# persephone_A_v1.net
KiCad netlist of a schematic drawn in EAGLE
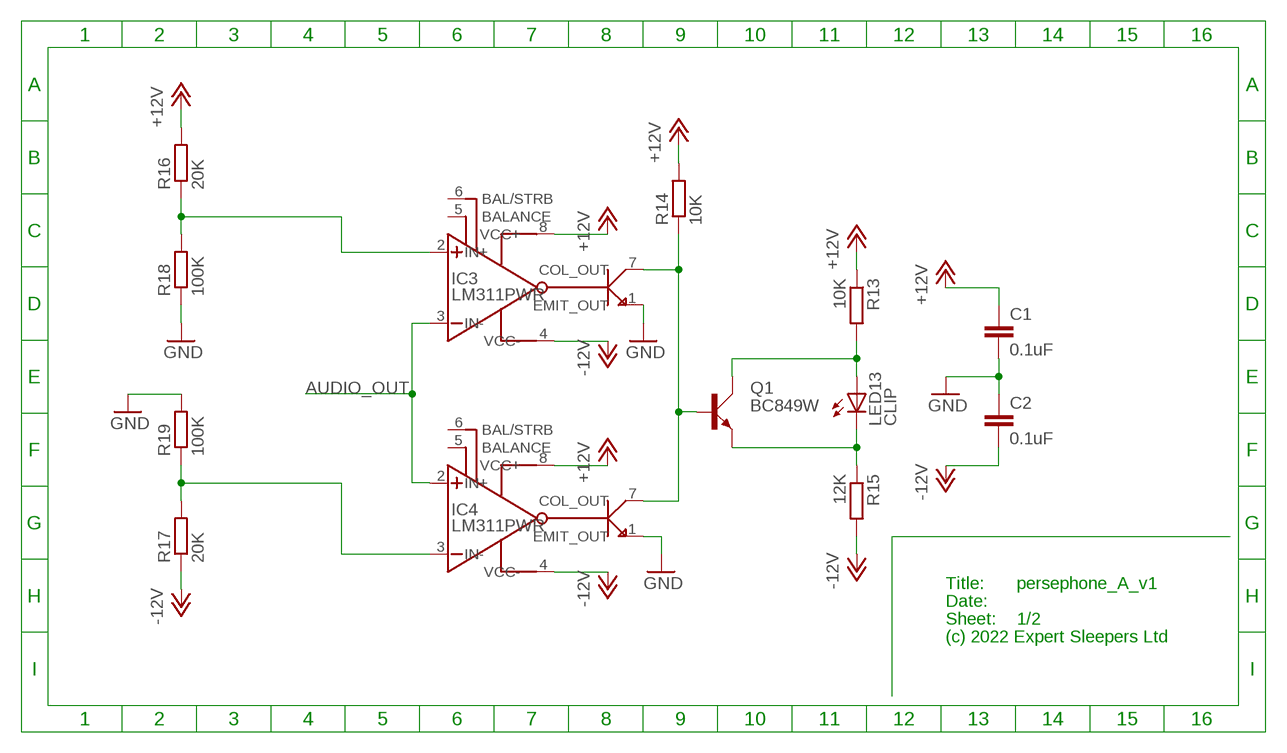
[diagram p0: schematic, sheet 1]
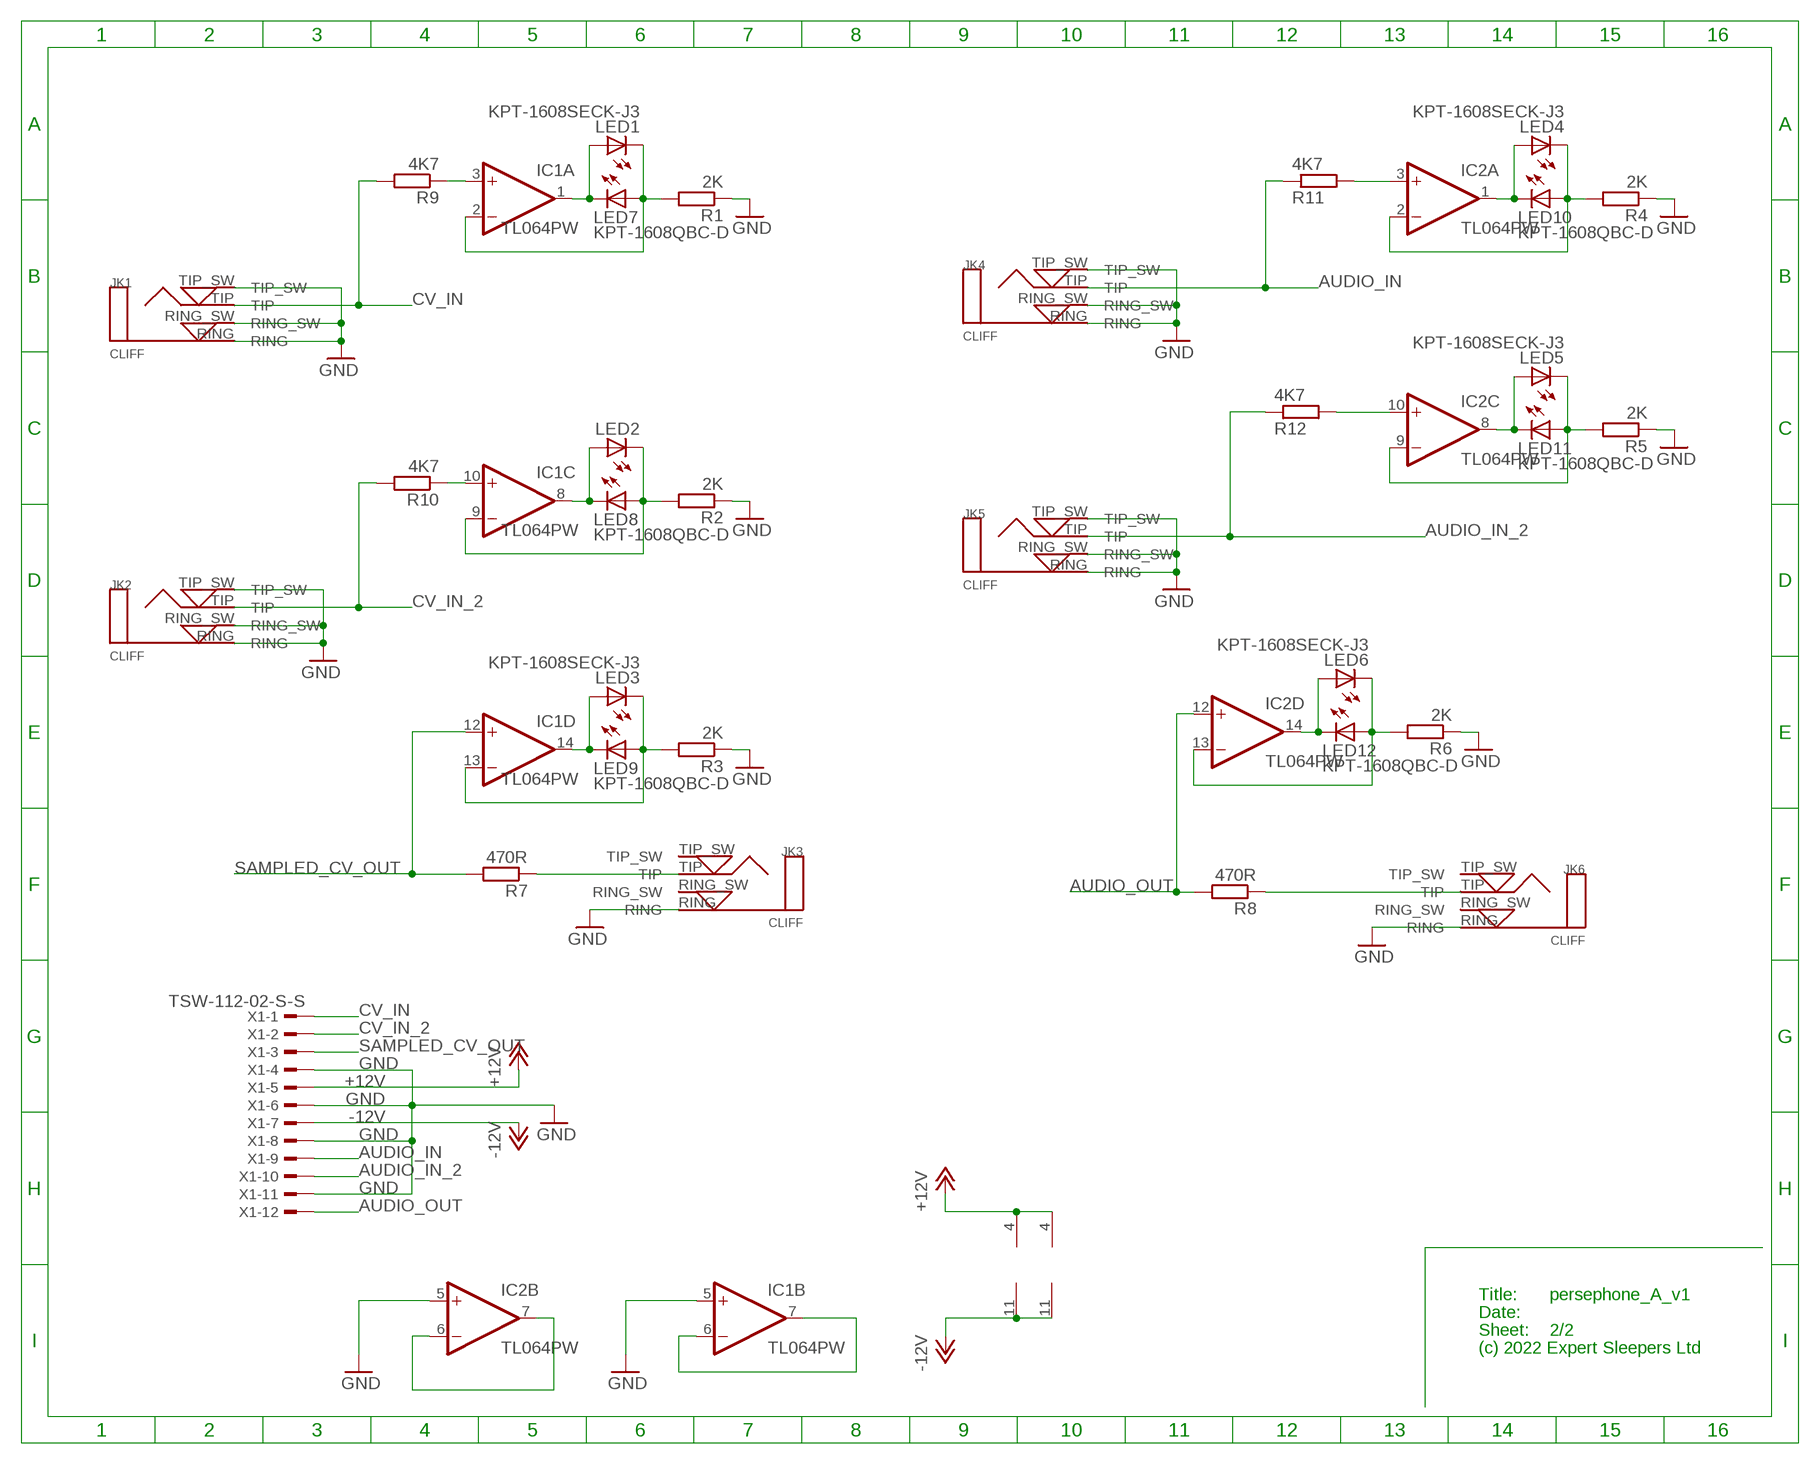
[diagram p1: schematic, sheet 2]

(export (version "E")
  (design (tool "Eeschema 10.0.6"))
  (components
    (comp (ref "IC1")
      (value "TL064PW")
      (footprint "eagle-import:PW_R-PDSO-G14")
      (libsource (lib "eagle-import") (part "TL074PW"))
    )
    (comp (ref "IC2")
      (value "TL064PW")
      (footprint "eagle-import:PW_R-PDSO-G14")
      (libsource (lib "eagle-import") (part "TL074PW"))
    )
    (comp (ref "JK1")
      (value "CLIFF")
      (footprint "eagle-import:CLIFF3.5MMPCB")
      (libsource (lib "eagle-import") (part "CLIFF3.5MM_PCB_SW_JK"))
    )
    (comp (ref "JK2")
      (value "CLIFF")
      (footprint "eagle-import:CLIFF3.5MMPCB")
      (libsource (lib "eagle-import") (part "CLIFF3.5MM_PCB_SW_JK"))
    )
    (comp (ref "JK3")
      (value "CLIFF")
      (footprint "eagle-import:CLIFF3.5MMPCB")
      (libsource (lib "eagle-import") (part "CLIFF3.5MM_PCB_SW_JK"))
    )
    (comp (ref "JK4")
      (value "CLIFF")
      (footprint "eagle-import:CLIFF3.5MMPCB")
      (libsource (lib "eagle-import") (part "CLIFF3.5MM_PCB_SW_JK"))
    )
    (comp (ref "JK5")
      (value "CLIFF")
      (footprint "eagle-import:CLIFF3.5MMPCB")
      (libsource (lib "eagle-import") (part "CLIFF3.5MM_PCB_SW_JK"))
    )
    (comp (ref "JK6")
      (value "CLIFF")
      (footprint "eagle-import:CLIFF3.5MMPCB")
      (libsource (lib "eagle-import") (part "CLIFF3.5MM_PCB_SW_JK"))
    )
    (comp (ref "LED1")
      (value "KPT-1608SECK-J3")
      (footprint "eagle-import:CHIPLED_0603_LEFT")
      (libsource (lib "eagle-import") (part "KPT-1608SECK-J3"))
    )
    (comp (ref "LED2")
      (value "KPT-1608SECK-J3")
      (footprint "eagle-import:CHIPLED_0603_LEFT")
      (libsource (lib "eagle-import") (part "KPT-1608SECK-J3"))
    )
    (comp (ref "LED3")
      (value "KPT-1608SECK-J3")
      (footprint "eagle-import:CHIPLED_0603_LEFT")
      (libsource (lib "eagle-import") (part "KPT-1608SECK-J3"))
    )
    (comp (ref "LED4")
      (value "KPT-1608SECK-J3")
      (footprint "eagle-import:CHIPLED_0603_LEFT")
      (libsource (lib "eagle-import") (part "KPT-1608SECK-J3"))
    )
    (comp (ref "LED5")
      (value "KPT-1608SECK-J3")
      (footprint "eagle-import:CHIPLED_0603_LEFT")
      (libsource (lib "eagle-import") (part "KPT-1608SECK-J3"))
    )
    (comp (ref "LED6")
      (value "KPT-1608SECK-J3")
      (footprint "eagle-import:CHIPLED_0603_LEFT")
      (libsource (lib "eagle-import") (part "KPT-1608SECK-J3"))
    )
    (comp (ref "LED7")
      (value "KPT-1608QBC-D")
      (footprint "eagle-import:CHIPLED_0603_RIGHT")
      (libsource (lib "eagle-import") (part "KPT-1608QBC-D"))
    )
    (comp (ref "LED8")
      (value "KPT-1608QBC-D")
      (footprint "eagle-import:CHIPLED_0603_RIGHT")
      (libsource (lib "eagle-import") (part "KPT-1608QBC-D"))
    )
    (comp (ref "LED9")
      (value "KPT-1608QBC-D")
      (footprint "eagle-import:CHIPLED_0603_RIGHT")
      (libsource (lib "eagle-import") (part "KPT-1608QBC-D"))
    )
    (comp (ref "LED10")
      (value "KPT-1608QBC-D")
      (footprint "eagle-import:CHIPLED_0603_RIGHT")
      (libsource (lib "eagle-import") (part "KPT-1608QBC-D"))
    )
    (comp (ref "LED11")
      (value "KPT-1608QBC-D")
      (footprint "eagle-import:CHIPLED_0603_RIGHT")
      (libsource (lib "eagle-import") (part "KPT-1608QBC-D"))
    )
    (comp (ref "LED12")
      (value "KPT-1608QBC-D")
      (footprint "eagle-import:CHIPLED_0603_RIGHT")
      (libsource (lib "eagle-import") (part "KPT-1608QBC-D"))
    )
    (comp (ref "R1")
      (value "2K")
      (footprint "eagle-import:R1206")
      (libsource (lib "eagle-import") (part "R-EU_R1206"))
    )
    (comp (ref "R2")
      (value "2K")
      (footprint "eagle-import:R1206")
      (libsource (lib "eagle-import") (part "R-EU_R1206"))
    )
    (comp (ref "R3")
      (value "2K")
      (footprint "eagle-import:R1206")
      (libsource (lib "eagle-import") (part "R-EU_R1206"))
    )
    (comp (ref "R4")
      (value "2K")
      (footprint "eagle-import:R1206")
      (libsource (lib "eagle-import") (part "R-EU_R1206"))
    )
    (comp (ref "R5")
      (value "2K")
      (footprint "eagle-import:R1206")
      (libsource (lib "eagle-import") (part "R-EU_R1206"))
    )
    (comp (ref "R6")
      (value "2K")
      (footprint "eagle-import:R1206")
      (libsource (lib "eagle-import") (part "R-EU_R1206"))
    )
    (comp (ref "R7")
      (value "470R")
      (footprint "eagle-import:R1206")
      (libsource (lib "eagle-import") (part "R-EU_R1206"))
    )
    (comp (ref "R8")
      (value "470R")
      (footprint "eagle-import:R1206")
      (libsource (lib "eagle-import") (part "R-EU_R1206"))
    )
    (comp (ref "R9")
      (value "4K7")
      (footprint "eagle-import:R1206")
      (libsource (lib "eagle-import") (part "R-EU_R1206"))
    )
    (comp (ref "R10")
      (value "4K7")
      (footprint "eagle-import:R1206")
      (libsource (lib "eagle-import") (part "R-EU_R1206"))
    )
    (comp (ref "R11")
      (value "4K7")
      (footprint "eagle-import:R1206")
      (libsource (lib "eagle-import") (part "R-EU_R1206"))
    )
    (comp (ref "R12")
      (value "4K7")
      (footprint "eagle-import:R1206")
      (libsource (lib "eagle-import") (part "R-EU_R1206"))
    )
    (comp (ref "X1")
      (value "TSW-112-02-S-S")
      (footprint "eagle-import:TSW-112-02-S-S")
      (libsource (lib "eagle-import") (part "TSW-112-02-S-S"))
    )
    (comp (ref "C1")
      (value "0.1uF")
      (footprint "eagle-import:C0402")
      (libsource (lib "eagle-import") (part "C-EUC0402"))
    )
    (comp (ref "C2")
      (value "0.1uF")
      (footprint "eagle-import:C0402")
      (libsource (lib "eagle-import") (part "C-EUC0402"))
    )
    (comp (ref "IC3")
      (value "LM311PWR")
      (footprint "eagle-import:SOP65P640X120-8N")
      (fields (field (name "MOUSER_PART_NUMBER") "595-LM311PWR"))
      (libsource (lib "eagle-import") (part "LM311PWR"))
    )
    (comp (ref "IC4")
      (value "LM311PWR")
      (footprint "eagle-import:SOP65P640X120-8N")
      (fields (field (name "MOUSER_PART_NUMBER") "595-LM311PWR"))
      (libsource (lib "eagle-import") (part "LM311PWR"))
    )
    (comp (ref "LED13")
      (value "CLIP")
      (footprint "eagle-import:L-710A8RS")
      (libsource (lib "eagle-import") (part "L-710A8RS/1SRD"))
    )
    (comp (ref "Q1")
      (value "BC849W")
      (footprint "eagle-import:SOT323")
      (libsource (lib "eagle-import") (part "BC849W"))
    )
    (comp (ref "R13")
      (value "10K")
      (footprint "eagle-import:R0603")
      (libsource (lib "eagle-import") (part "R-EU_R0603"))
    )
    (comp (ref "R14")
      (value "10K")
      (footprint "eagle-import:R0603")
      (libsource (lib "eagle-import") (part "R-EU_R0603"))
    )
    (comp (ref "R15")
      (value "12K")
      (footprint "eagle-import:R0603")
      (libsource (lib "eagle-import") (part "R-EU_R0603"))
    )
    (comp (ref "R16")
      (value "20K")
      (footprint "eagle-import:R0603")
      (libsource (lib "eagle-import") (part "R-EU_R0603"))
    )
    (comp (ref "R17")
      (value "20K")
      (footprint "eagle-import:R0603")
      (libsource (lib "eagle-import") (part "R-EU_R0603"))
    )
    (comp (ref "R18")
      (value "100K")
      (footprint "eagle-import:R0603")
      (libsource (lib "eagle-import") (part "R-EU_R0603"))
    )
    (comp (ref "R19")
      (value "100K")
      (footprint "eagle-import:R0603")
      (libsource (lib "eagle-import") (part "R-EU_R0603"))
    )
  )
  (nets
    (net (code "1") (name "+12V") (class "Default")
      (node (ref "C1") (pin "1") (pinfunction "1_1") (pintype "passive"))
      (node (ref "IC1") (pin "4") (pinfunction "V+_4") (pintype "power_in"))
      (node (ref "IC2") (pin "4") (pinfunction "V+_4") (pintype "power_in"))
      (node (ref "IC3") (pin "8") (pinfunction "VCC+_8") (pintype "power_in"))
      (node (ref "IC4") (pin "8") (pinfunction "VCC+_8") (pintype "power_in"))
      (node (ref "R13") (pin "1") (pinfunction "1_1") (pintype "passive"))
      (node (ref "R14") (pin "2") (pinfunction "2_2") (pintype "passive"))
      (node (ref "R16") (pin "2") (pinfunction "2_2") (pintype "passive"))
      (node (ref "X1") (pin "5") (pinfunction "1_5") (pintype "passive"))
    )
    (net (code "2") (name "-12V") (class "Default")
      (node (ref "C2") (pin "2") (pinfunction "2_2") (pintype "passive"))
      (node (ref "IC1") (pin "11") (pinfunction "V-_11") (pintype "power_in"))
      (node (ref "IC2") (pin "11") (pinfunction "V-_11") (pintype "power_in"))
      (node (ref "IC3") (pin "4") (pinfunction "VCC-_4") (pintype "power_in"))
      (node (ref "IC4") (pin "4") (pinfunction "VCC-_4") (pintype "power_in"))
      (node (ref "R15") (pin "2") (pinfunction "2_2") (pintype "passive"))
      (node (ref "R17") (pin "1") (pinfunction "1_1") (pintype "passive"))
      (node (ref "X1") (pin "7") (pinfunction "1_7") (pintype "passive"))
    )
    (net (code "3") (name "AUDIO_IN") (class "Default")
      (node (ref "JK4") (pin "TIP") (pinfunction "TIP_TIP") (pintype "bidirectional"))
      (node (ref "R11") (pin "1") (pinfunction "1_1") (pintype "passive"))
      (node (ref "X1") (pin "9") (pinfunction "1_9") (pintype "passive"))
    )
    (net (code "4") (name "AUDIO_IN_2") (class "Default")
      (node (ref "JK5") (pin "TIP") (pinfunction "TIP_TIP") (pintype "bidirectional"))
      (node (ref "R12") (pin "1") (pinfunction "1_1") (pintype "passive"))
      (node (ref "X1") (pin "10") (pinfunction "1_10") (pintype "passive"))
    )
    (net (code "5") (name "AUDIO_OUT") (class "Default")
      (node (ref "IC2") (pin "12") (pinfunction "+IN_12") (pintype "input"))
      (node (ref "IC3") (pin "3") (pinfunction "IN-_3") (pintype "input"))
      (node (ref "IC4") (pin "2") (pinfunction "IN+_2") (pintype "input"))
      (node (ref "R8") (pin "2") (pinfunction "2_2") (pintype "passive"))
      (node (ref "X1") (pin "12") (pinfunction "1_12") (pintype "passive"))
    )
    (net (code "6") (name "CV_IN") (class "Default")
      (node (ref "JK1") (pin "TIP") (pinfunction "TIP_TIP") (pintype "bidirectional"))
      (node (ref "R9") (pin "2") (pinfunction "2_2") (pintype "passive"))
      (node (ref "X1") (pin "1") (pinfunction "1_1") (pintype "passive"))
    )
    (net (code "7") (name "CV_IN_2") (class "Default")
      (node (ref "JK2") (pin "TIP") (pinfunction "TIP_TIP") (pintype "bidirectional"))
      (node (ref "R10") (pin "2") (pinfunction "2_2") (pintype "passive"))
      (node (ref "X1") (pin "2") (pinfunction "1_2") (pintype "passive"))
    )
    (net (code "8") (name "GND") (class "Default")
      (node (ref "C1") (pin "2") (pinfunction "2_2") (pintype "passive"))
      (node (ref "C2") (pin "1") (pinfunction "1_1") (pintype "passive"))
      (node (ref "IC1") (pin "5") (pinfunction "+IN_5") (pintype "input"))
      (node (ref "IC2") (pin "5") (pinfunction "+IN_5") (pintype "input"))
      (node (ref "IC3") (pin "1") (pinfunction "EMIT_OUT_1") (pintype "bidirectional"))
      (node (ref "IC4") (pin "1") (pinfunction "EMIT_OUT_1") (pintype "bidirectional"))
      (node (ref "JK1") (pin "RING") (pinfunction "RING_RING") (pintype "bidirectional"))
      (node (ref "JK1") (pin "RING_SW") (pinfunction "RING_SW_RING_SW") (pintype "bidirectional"))
      (node (ref "JK1") (pin "TIP_SW") (pinfunction "TIP_SW_TIP_SW") (pintype "bidirectional"))
      (node (ref "JK2") (pin "RING") (pinfunction "RING_RING") (pintype "bidirectional"))
      (node (ref "JK2") (pin "RING_SW") (pinfunction "RING_SW_RING_SW") (pintype "bidirectional"))
      (node (ref "JK2") (pin "TIP_SW") (pinfunction "TIP_SW_TIP_SW") (pintype "bidirectional"))
      (node (ref "JK3") (pin "RING") (pinfunction "RING_RING") (pintype "bidirectional"))
      (node (ref "JK4") (pin "RING") (pinfunction "RING_RING") (pintype "bidirectional"))
      (node (ref "JK4") (pin "RING_SW") (pinfunction "RING_SW_RING_SW") (pintype "bidirectional"))
      (node (ref "JK4") (pin "TIP_SW") (pinfunction "TIP_SW_TIP_SW") (pintype "bidirectional"))
      (node (ref "JK5") (pin "RING") (pinfunction "RING_RING") (pintype "bidirectional"))
      (node (ref "JK5") (pin "RING_SW") (pinfunction "RING_SW_RING_SW") (pintype "bidirectional"))
      (node (ref "JK5") (pin "TIP_SW") (pinfunction "TIP_SW_TIP_SW") (pintype "bidirectional"))
      (node (ref "JK6") (pin "RING") (pinfunction "RING_RING") (pintype "bidirectional"))
      (node (ref "R1") (pin "1") (pinfunction "1_1") (pintype "passive"))
      (node (ref "R18") (pin "1") (pinfunction "1_1") (pintype "passive"))
      (node (ref "R19") (pin "2") (pinfunction "2_2") (pintype "passive"))
      (node (ref "R2") (pin "1") (pinfunction "1_1") (pintype "passive"))
      (node (ref "R3") (pin "1") (pinfunction "1_1") (pintype "passive"))
      (node (ref "R4") (pin "1") (pinfunction "1_1") (pintype "passive"))
      (node (ref "R5") (pin "1") (pinfunction "1_1") (pintype "passive"))
      (node (ref "R6") (pin "1") (pinfunction "1_1") (pintype "passive"))
      (node (ref "X1") (pin "11") (pinfunction "1_11") (pintype "passive"))
      (node (ref "X1") (pin "4") (pinfunction "1_4") (pintype "passive"))
      (node (ref "X1") (pin "6") (pinfunction "1_6") (pintype "passive"))
      (node (ref "X1") (pin "8") (pinfunction "1_8") (pintype "passive"))
    )
    (net (code "9") (name "Net-(IC1A-+IN)") (class "Default")
      (node (ref "IC1") (pin "3") (pinfunction "+IN_3") (pintype "input"))
      (node (ref "R9") (pin "1") (pinfunction "1_1") (pintype "passive"))
    )
    (net (code "10") (name "Net-(IC1A--IN)") (class "Default")
      (node (ref "IC1") (pin "2") (pinfunction "-IN_2") (pintype "input"))
      (node (ref "LED1") (pin "1") (pinfunction "C_1") (pintype "passive"))
      (node (ref "LED7") (pin "1") (pinfunction "A_1") (pintype "passive"))
      (node (ref "R1") (pin "2") (pinfunction "2_2") (pintype "passive"))
    )
    (net (code "11") (name "Net-(IC1A-OUT)") (class "Default")
      (node (ref "IC1") (pin "1") (pinfunction "OUT_1") (pintype "output"))
      (node (ref "LED1") (pin "2") (pinfunction "A_2") (pintype "passive"))
      (node (ref "LED7") (pin "2") (pinfunction "C_2") (pintype "passive"))
    )
    (net (code "12") (name "Net-(IC1B--IN)") (class "Default")
      (node (ref "IC1") (pin "6") (pinfunction "-IN_6") (pintype "input"))
      (node (ref "IC1") (pin "7") (pinfunction "OUT_7") (pintype "output"))
    )
    (net (code "13") (name "Net-(IC1C-+IN)") (class "Default")
      (node (ref "IC1") (pin "10") (pinfunction "+IN_10") (pintype "input"))
      (node (ref "R10") (pin "1") (pinfunction "1_1") (pintype "passive"))
    )
    (net (code "14") (name "Net-(IC1C--IN)") (class "Default")
      (node (ref "IC1") (pin "9") (pinfunction "-IN_9") (pintype "input"))
      (node (ref "LED2") (pin "1") (pinfunction "C_1") (pintype "passive"))
      (node (ref "LED8") (pin "1") (pinfunction "A_1") (pintype "passive"))
      (node (ref "R2") (pin "2") (pinfunction "2_2") (pintype "passive"))
    )
    (net (code "15") (name "Net-(IC1C-OUT)") (class "Default")
      (node (ref "IC1") (pin "8") (pinfunction "OUT_8") (pintype "output"))
      (node (ref "LED2") (pin "2") (pinfunction "A_2") (pintype "passive"))
      (node (ref "LED8") (pin "2") (pinfunction "C_2") (pintype "passive"))
    )
    (net (code "16") (name "Net-(IC1D--IN)") (class "Default")
      (node (ref "IC1") (pin "13") (pinfunction "-IN_13") (pintype "input"))
      (node (ref "LED3") (pin "1") (pinfunction "C_1") (pintype "passive"))
      (node (ref "LED9") (pin "1") (pinfunction "A_1") (pintype "passive"))
      (node (ref "R3") (pin "2") (pinfunction "2_2") (pintype "passive"))
    )
    (net (code "17") (name "Net-(IC1D-OUT)") (class "Default")
      (node (ref "IC1") (pin "14") (pinfunction "OUT_14") (pintype "output"))
      (node (ref "LED3") (pin "2") (pinfunction "A_2") (pintype "passive"))
      (node (ref "LED9") (pin "2") (pinfunction "C_2") (pintype "passive"))
    )
    (net (code "18") (name "Net-(IC2A-+IN)") (class "Default")
      (node (ref "IC2") (pin "3") (pinfunction "+IN_3") (pintype "input"))
      (node (ref "R11") (pin "2") (pinfunction "2_2") (pintype "passive"))
    )
    (net (code "19") (name "Net-(IC2A--IN)") (class "Default")
      (node (ref "IC2") (pin "2") (pinfunction "-IN_2") (pintype "input"))
      (node (ref "LED10") (pin "1") (pinfunction "A_1") (pintype "passive"))
      (node (ref "LED4") (pin "1") (pinfunction "C_1") (pintype "passive"))
      (node (ref "R4") (pin "2") (pinfunction "2_2") (pintype "passive"))
    )
    (net (code "20") (name "Net-(IC2A-OUT)") (class "Default")
      (node (ref "IC2") (pin "1") (pinfunction "OUT_1") (pintype "output"))
      (node (ref "LED10") (pin "2") (pinfunction "C_2") (pintype "passive"))
      (node (ref "LED4") (pin "2") (pinfunction "A_2") (pintype "passive"))
    )
    (net (code "21") (name "Net-(IC2B--IN)") (class "Default")
      (node (ref "IC2") (pin "6") (pinfunction "-IN_6") (pintype "input"))
      (node (ref "IC2") (pin "7") (pinfunction "OUT_7") (pintype "output"))
    )
    (net (code "22") (name "Net-(IC2C-+IN)") (class "Default")
      (node (ref "IC2") (pin "10") (pinfunction "+IN_10") (pintype "input"))
      (node (ref "R12") (pin "2") (pinfunction "2_2") (pintype "passive"))
    )
    (net (code "23") (name "Net-(IC2C--IN)") (class "Default")
      (node (ref "IC2") (pin "9") (pinfunction "-IN_9") (pintype "input"))
      (node (ref "LED11") (pin "1") (pinfunction "A_1") (pintype "passive"))
      (node (ref "LED5") (pin "1") (pinfunction "C_1") (pintype "passive"))
      (node (ref "R5") (pin "2") (pinfunction "2_2") (pintype "passive"))
    )
    (net (code "24") (name "Net-(IC2C-OUT)") (class "Default")
      (node (ref "IC2") (pin "8") (pinfunction "OUT_8") (pintype "output"))
      (node (ref "LED11") (pin "2") (pinfunction "C_2") (pintype "passive"))
      (node (ref "LED5") (pin "2") (pinfunction "A_2") (pintype "passive"))
    )
    (net (code "25") (name "Net-(IC2D--IN)") (class "Default")
      (node (ref "IC2") (pin "13") (pinfunction "-IN_13") (pintype "input"))
      (node (ref "LED12") (pin "1") (pinfunction "A_1") (pintype "passive"))
      (node (ref "LED6") (pin "1") (pinfunction "C_1") (pintype "passive"))
      (node (ref "R6") (pin "2") (pinfunction "2_2") (pintype "passive"))
    )
    (net (code "26") (name "Net-(IC2D-OUT)") (class "Default")
      (node (ref "IC2") (pin "14") (pinfunction "OUT_14") (pintype "output"))
      (node (ref "LED12") (pin "2") (pinfunction "C_2") (pintype "passive"))
      (node (ref "LED6") (pin "2") (pinfunction "A_2") (pintype "passive"))
    )
    (net (code "27") (name "Net-(IC3-COL_OUT)") (class "Default")
      (node (ref "IC3") (pin "7") (pinfunction "COL_OUT_7") (pintype "bidirectional"))
      (node (ref "IC4") (pin "7") (pinfunction "COL_OUT_7") (pintype "bidirectional"))
      (node (ref "Q1") (pin "1") (pinfunction "B_1") (pintype "passive"))
      (node (ref "R14") (pin "1") (pinfunction "1_1") (pintype "passive"))
    )
    (net (code "28") (name "Net-(IC3-IN+)") (class "Default")
      (node (ref "IC3") (pin "2") (pinfunction "IN+_2") (pintype "input"))
      (node (ref "R16") (pin "1") (pinfunction "1_1") (pintype "passive"))
      (node (ref "R18") (pin "2") (pinfunction "2_2") (pintype "passive"))
    )
    (net (code "29") (name "Net-(IC4-IN-)") (class "Default")
      (node (ref "IC4") (pin "3") (pinfunction "IN-_3") (pintype "input"))
      (node (ref "R17") (pin "2") (pinfunction "2_2") (pintype "passive"))
      (node (ref "R19") (pin "1") (pinfunction "1_1") (pintype "passive"))
    )
    (net (code "30") (name "Net-(JK3-PadTIP)") (class "Default")
      (node (ref "JK3") (pin "TIP") (pinfunction "TIP_TIP") (pintype "bidirectional"))
      (node (ref "R7") (pin "1") (pinfunction "1_1") (pintype "passive"))
    )
    (net (code "31") (name "Net-(JK6-PadTIP)") (class "Default")
      (node (ref "JK6") (pin "TIP") (pinfunction "TIP_TIP") (pintype "bidirectional"))
      (node (ref "R8") (pin "1") (pinfunction "1_1") (pintype "passive"))
    )
    (net (code "32") (name "Net-(Q1-C)") (class "Default")
      (node (ref "LED13") (pin "A") (pinfunction "A_A") (pintype "passive"))
      (node (ref "Q1") (pin "3") (pinfunction "C_3") (pintype "passive"))
      (node (ref "R13") (pin "2") (pinfunction "2_2") (pintype "passive"))
    )
    (net (code "33") (name "Net-(Q1-E)") (class "Default")
      (node (ref "LED13") (pin "C") (pinfunction "C_C") (pintype "passive"))
      (node (ref "Q1") (pin "2") (pinfunction "E_2") (pintype "passive"))
      (node (ref "R15") (pin "1") (pinfunction "1_1") (pintype "passive"))
    )
    (net (code "34") (name "SAMPLED_CV_OUT") (class "Default")
      (node (ref "IC1") (pin "12") (pinfunction "+IN_12") (pintype "input"))
      (node (ref "R7") (pin "2") (pinfunction "2_2") (pintype "passive"))
      (node (ref "X1") (pin "3") (pinfunction "1_3") (pintype "passive"))
    )
    (net (code "35") (name "unconnected-(IC3-BALANCE-Pad5)") (class "Default")
      (node (ref "IC3") (pin "5") (pinfunction "BALANCE_5") (pintype "bidirectional"))
    )
    (net (code "36") (name "unconnected-(IC3-BAL{slash}STRB-Pad6)") (class "Default")
      (node (ref "IC3") (pin "6") (pinfunction "BAL/STRB_6") (pintype "bidirectional"))
    )
    (net (code "37") (name "unconnected-(IC4-BALANCE-Pad5)") (class "Default")
      (node (ref "IC4") (pin "5") (pinfunction "BALANCE_5") (pintype "bidirectional"))
    )
    (net (code "38") (name "unconnected-(IC4-BAL{slash}STRB-Pad6)") (class "Default")
      (node (ref "IC4") (pin "6") (pinfunction "BAL/STRB_6") (pintype "bidirectional"))
    )
    (net (code "39") (name "unconnected-(JK3-PadRING_SW)") (class "Default")
      (node (ref "JK3") (pin "RING_SW") (pinfunction "RING_SW_RING_SW") (pintype "bidirectional"))
    )
    (net (code "40") (name "unconnected-(JK3-PadTIP_SW)") (class "Default")
      (node (ref "JK3") (pin "TIP_SW") (pinfunction "TIP_SW_TIP_SW") (pintype "bidirectional"))
    )
    (net (code "41") (name "unconnected-(JK6-PadRING_SW)") (class "Default")
      (node (ref "JK6") (pin "RING_SW") (pinfunction "RING_SW_RING_SW") (pintype "bidirectional"))
    )
    (net (code "42") (name "unconnected-(JK6-PadTIP_SW)") (class "Default")
      (node (ref "JK6") (pin "TIP_SW") (pinfunction "TIP_SW_TIP_SW") (pintype "bidirectional"))
    )
  )
)
